# Digital_Psu.net
KiCad netlist of a schematic drawn in Altium Designer
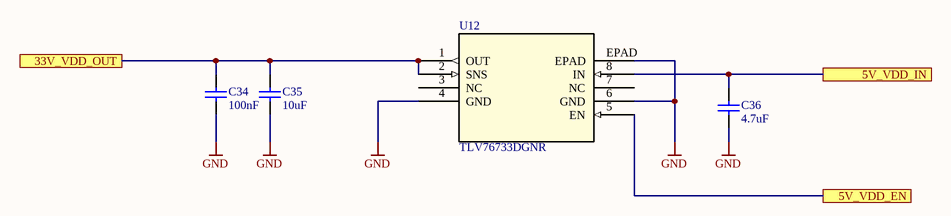
[diagram p0: Digital_Psu.SchDoc]

(export (version "E")
  (design (tool "Eeschema 10.0.6"))
  (components
    (comp (ref "C34")
      (value "100nF")
      (footprint "C1206-KUE")
      (description "Capacitor")
      (fields (field (name "MANUFACTURER") "Kemet") (field (name "PUBLISHER") "Altium Limited"))
      (libsource (lib "ExtrapartsKUE_V01") (part "Capacitor"))
    )
    (comp (ref "C35")
      (value "10uF")
      (footprint "C1206-KUE")
      (description "Capacitor")
      (fields (field (name "MANUFACTURER") "Kemet") (field (name "PUBLISHER") "Altium Limited"))
      (libsource (lib "ExtrapartsKUE_V01") (part "Capacitor"))
    )
    (comp (ref "C36")
      (value "4.7uF")
      (footprint "C1206-KUE")
      (description "Capacitor")
      (fields (field (name "MANUFACTURER") "Kemet") (field (name "PUBLISHER") "Altium Limited"))
      (libsource (lib "ExtrapartsKUE_V01") (part "Capacitor"))
    )
    (comp (ref "U12")
      (value "TLV76733DGNR")
      (footprint "VSSOP8_DGN_TEX")
      (fields (field (name "COPYRIGHT") "Copyright (C) 2025 Ultra Librarian. All rights reserved."))
      (libsource (lib "TLV76733DGNR") (part "TLV76733DGNR"))
    )
  )
  (nets
    (net (code "1") (name "/5V_VDD_EN") (class "Default")
      (node (ref "U12") (pin "5") (pinfunction "EN_5") (pintype "input"))
    )
    (net (code "2") (name "/5V_VDD_IN") (class "Default")
      (node (ref "C36") (pin "2") (pinfunction "2_2") (pintype "passive"))
      (node (ref "U12") (pin "8") (pinfunction "IN_8") (pintype "input"))
    )
    (net (code "3") (name "/33V_VDD_OUT") (class "Default")
      (node (ref "C34") (pin "2") (pinfunction "2_2") (pintype "passive"))
      (node (ref "C35") (pin "2") (pinfunction "2_2") (pintype "passive"))
      (node (ref "U12") (pin "1") (pinfunction "OUT_1") (pintype "output"))
      (node (ref "U12") (pin "2") (pinfunction "SNS_2") (pintype "input"))
    )
    (net (code "4") (name "GND") (class "Default")
      (node (ref "C34") (pin "1") (pinfunction "1_1") (pintype "passive"))
      (node (ref "C35") (pin "1") (pinfunction "1_1") (pintype "passive"))
      (node (ref "C36") (pin "1") (pinfunction "1_1") (pintype "passive"))
      (node (ref "U12") (pin "4") (pinfunction "GND_4") (pintype "power_in"))
      (node (ref "U12") (pin "6") (pinfunction "GND_6") (pintype "power_in"))
      (node (ref "U12") (pin "EPAD") (pinfunction "EPAD_EPAD") (pintype "power_in"))
    )
    (net (code "5") (name "unconnected-(U12-NC-Pad3)") (class "Default")
      (node (ref "U12") (pin "3") (pinfunction "NC_3") (pintype "passive"))
    )
    (net (code "6") (name "unconnected-(U12-NC-Pad7)") (class "Default")
      (node (ref "U12") (pin "7") (pinfunction "NC_7") (pintype "passive"))
    )
  )
)
